# Drive_7seg.net
KiCad netlist of a schematic drawn in EAGLE
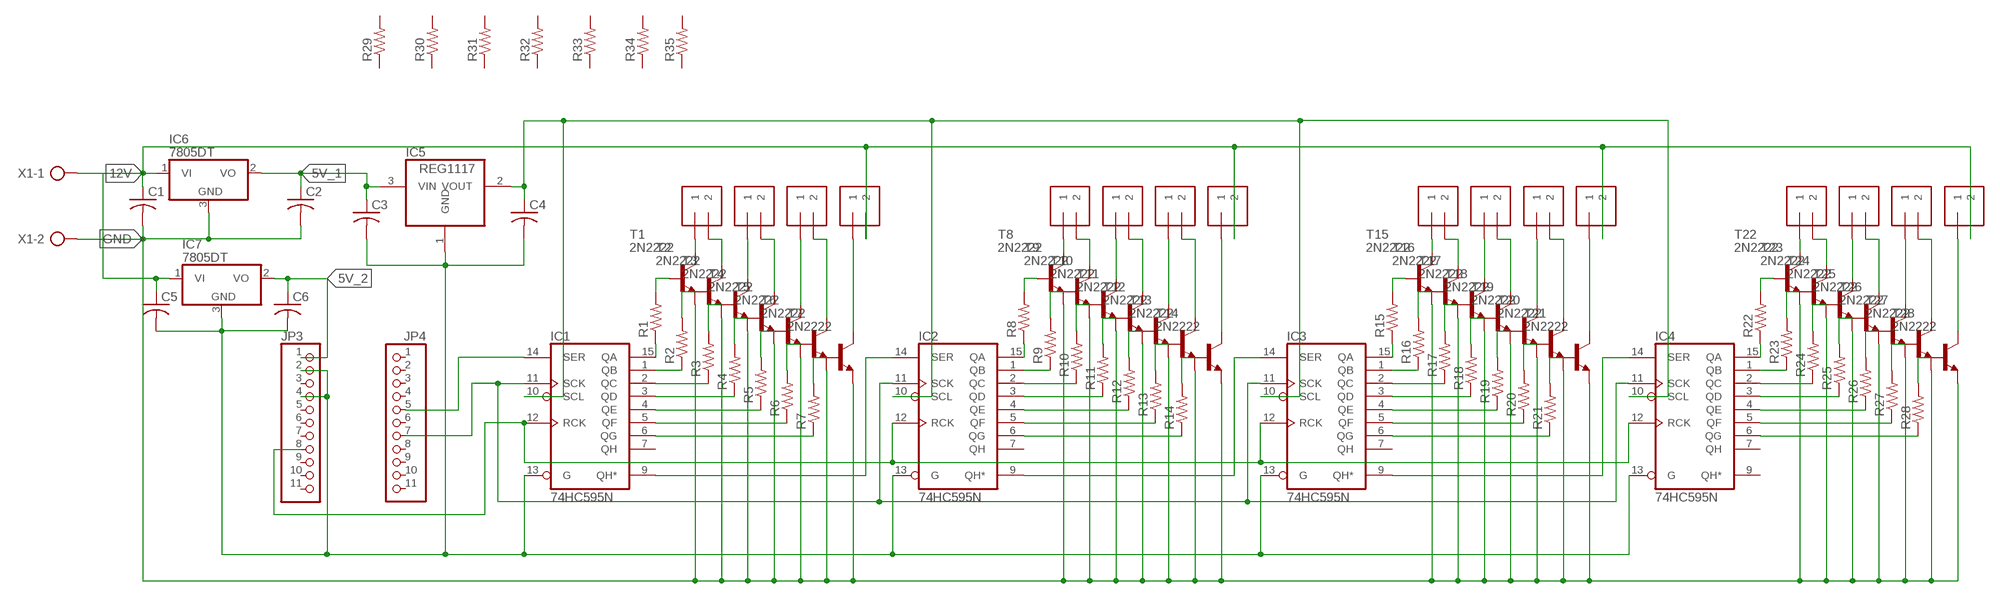
[diagram p0: schematic, sheet 1]

(export (version "E")
  (design (tool "Eeschema 10.0.6"))
  (components
    (comp (ref "C1")
      (value "C-USC0805K")
      (footprint "eagle-import:C0805K")
      (libsource (lib "eagle-import") (part "C-USC0805K"))
    )
    (comp (ref "C2")
      (value "C-USC0805K")
      (footprint "eagle-import:C0805K")
      (libsource (lib "eagle-import") (part "C-USC0805K"))
    )
    (comp (ref "C3")
      (value "C-USC0805K")
      (footprint "eagle-import:C0805K")
      (libsource (lib "eagle-import") (part "C-USC0805K"))
    )
    (comp (ref "C4")
      (value "C-USC0805K")
      (footprint "eagle-import:C0805K")
      (libsource (lib "eagle-import") (part "C-USC0805K"))
    )
    (comp (ref "C5")
      (value "C-USC0805K")
      (footprint "eagle-import:C0805K")
      (libsource (lib "eagle-import") (part "C-USC0805K"))
    )
    (comp (ref "C6")
      (value "C-USC0805K")
      (footprint "eagle-import:C0805K")
      (libsource (lib "eagle-import") (part "C-USC0805K"))
    )
    (comp (ref "IC1")
      (value "74HC595N")
      (footprint "eagle-import:DIL16")
      (libsource (lib "eagle-import") (part "74595NHC"))
    )
    (comp (ref "IC2")
      (value "74HC595N")
      (footprint "eagle-import:DIL16")
      (libsource (lib "eagle-import") (part "74595NHC"))
    )
    (comp (ref "IC3")
      (value "74HC595N")
      (footprint "eagle-import:DIL16")
      (libsource (lib "eagle-import") (part "74595NHC"))
    )
    (comp (ref "IC4")
      (value "74HC595N")
      (footprint "eagle-import:DIL16")
      (libsource (lib "eagle-import") (part "74595NHC"))
    )
    (comp (ref "IC5")
      (value "REG1117")
      (footprint "eagle-import:SOT223")
      (libsource (lib "eagle-import") (part "REG1117"))
    )
    (comp (ref "IC6")
      (value "7805DT")
      (footprint "eagle-import:TO252")
      (libsource (lib "eagle-import") (part "78DT05"))
    )
    (comp (ref "IC7")
      (value "7805DT")
      (footprint "eagle-import:TO252")
      (libsource (lib "eagle-import") (part "78DT05"))
    )
    (comp (ref "J1")
      (value "1X2-3.5MM")
      (footprint "eagle-import:1X2-3.5MM")
      (libsource (lib "eagle-import") (part "1X2-3.5MM"))
    )
    (comp (ref "J2")
      (value "1X2-3.5MM")
      (footprint "eagle-import:1X2-3.5MM")
      (libsource (lib "eagle-import") (part "1X2-3.5MM"))
    )
    (comp (ref "J3")
      (value "1X2-3.5MM")
      (footprint "eagle-import:1X2-3.5MM")
      (libsource (lib "eagle-import") (part "1X2-3.5MM"))
    )
    (comp (ref "J4")
      (value "1X2-3.5MM")
      (footprint "eagle-import:1X2-3.5MM")
      (libsource (lib "eagle-import") (part "1X2-3.5MM"))
    )
    (comp (ref "J5")
      (value "1X2-3.5MM")
      (footprint "eagle-import:1X2-3.5MM")
      (libsource (lib "eagle-import") (part "1X2-3.5MM"))
    )
    (comp (ref "J6")
      (value "1X2-3.5MM")
      (footprint "eagle-import:1X2-3.5MM")
      (libsource (lib "eagle-import") (part "1X2-3.5MM"))
    )
    (comp (ref "J7")
      (value "1X2-3.5MM")
      (footprint "eagle-import:1X2-3.5MM")
      (libsource (lib "eagle-import") (part "1X2-3.5MM"))
    )
    (comp (ref "J8")
      (value "1X2-3.5MM")
      (footprint "eagle-import:1X2-3.5MM")
      (libsource (lib "eagle-import") (part "1X2-3.5MM"))
    )
    (comp (ref "J9")
      (value "1X2-3.5MM")
      (footprint "eagle-import:1X2-3.5MM")
      (libsource (lib "eagle-import") (part "1X2-3.5MM"))
    )
    (comp (ref "J10")
      (value "1X2-3.5MM")
      (footprint "eagle-import:1X2-3.5MM")
      (libsource (lib "eagle-import") (part "1X2-3.5MM"))
    )
    (comp (ref "J11")
      (value "1X2-3.5MM")
      (footprint "eagle-import:1X2-3.5MM")
      (libsource (lib "eagle-import") (part "1X2-3.5MM"))
    )
    (comp (ref "J12")
      (value "1X2-3.5MM")
      (footprint "eagle-import:1X2-3.5MM")
      (libsource (lib "eagle-import") (part "1X2-3.5MM"))
    )
    (comp (ref "J13")
      (value "1X2-3.5MM")
      (footprint "eagle-import:1X2-3.5MM")
      (libsource (lib "eagle-import") (part "1X2-3.5MM"))
    )
    (comp (ref "J14")
      (value "1X2-3.5MM")
      (footprint "eagle-import:1X2-3.5MM")
      (libsource (lib "eagle-import") (part "1X2-3.5MM"))
    )
    (comp (ref "J15")
      (value "1X2-3.5MM")
      (footprint "eagle-import:1X2-3.5MM")
      (libsource (lib "eagle-import") (part "1X2-3.5MM"))
    )
    (comp (ref "J16")
      (value "1X2-3.5MM")
      (footprint "eagle-import:1X2-3.5MM")
      (libsource (lib "eagle-import") (part "1X2-3.5MM"))
    )
    (comp (ref "JP3")
      (value "PINHD-1X11")
      (footprint "eagle-import:1X11")
      (libsource (lib "eagle-import") (part "PINHD-1X11"))
    )
    (comp (ref "JP4")
      (value "PINHD-1X11")
      (footprint "eagle-import:1X11")
      (libsource (lib "eagle-import") (part "PINHD-1X11"))
    )
    (comp (ref "R1")
      (value "R-US_0204/7")
      (footprint "eagle-import:0204_7")
      (libsource (lib "eagle-import") (part "R-US_0204/7"))
    )
    (comp (ref "R2")
      (value "R-US_0204/7")
      (footprint "eagle-import:0204_7")
      (libsource (lib "eagle-import") (part "R-US_0204/7"))
    )
    (comp (ref "R3")
      (value "R-US_0204/7")
      (footprint "eagle-import:0204_7")
      (libsource (lib "eagle-import") (part "R-US_0204/7"))
    )
    (comp (ref "R4")
      (value "R-US_0204/7")
      (footprint "eagle-import:0204_7")
      (libsource (lib "eagle-import") (part "R-US_0204/7"))
    )
    (comp (ref "R5")
      (value "R-US_0204/7")
      (footprint "eagle-import:0204_7")
      (libsource (lib "eagle-import") (part "R-US_0204/7"))
    )
    (comp (ref "R6")
      (value "R-US_0204/7")
      (footprint "eagle-import:0204_7")
      (libsource (lib "eagle-import") (part "R-US_0204/7"))
    )
    (comp (ref "R7")
      (value "R-US_0204/7")
      (footprint "eagle-import:0204_7")
      (libsource (lib "eagle-import") (part "R-US_0204/7"))
    )
    (comp (ref "R8")
      (value "R-US_0204/7")
      (footprint "eagle-import:0204_7")
      (libsource (lib "eagle-import") (part "R-US_0204/7"))
    )
    (comp (ref "R9")
      (value "R-US_0204/7")
      (footprint "eagle-import:0204_7")
      (libsource (lib "eagle-import") (part "R-US_0204/7"))
    )
    (comp (ref "R10")
      (value "R-US_0204/7")
      (footprint "eagle-import:0204_7")
      (libsource (lib "eagle-import") (part "R-US_0204/7"))
    )
    (comp (ref "R11")
      (value "R-US_0204/7")
      (footprint "eagle-import:0204_7")
      (libsource (lib "eagle-import") (part "R-US_0204/7"))
    )
    (comp (ref "R12")
      (value "R-US_0204/7")
      (footprint "eagle-import:0204_7")
      (libsource (lib "eagle-import") (part "R-US_0204/7"))
    )
    (comp (ref "R13")
      (value "R-US_0204/7")
      (footprint "eagle-import:0204_7")
      (libsource (lib "eagle-import") (part "R-US_0204/7"))
    )
    (comp (ref "R14")
      (value "R-US_0204/7")
      (footprint "eagle-import:0204_7")
      (libsource (lib "eagle-import") (part "R-US_0204/7"))
    )
    (comp (ref "R15")
      (value "R-US_0204/7")
      (footprint "eagle-import:0204_7")
      (libsource (lib "eagle-import") (part "R-US_0204/7"))
    )
    (comp (ref "R16")
      (value "R-US_0204/7")
      (footprint "eagle-import:0204_7")
      (libsource (lib "eagle-import") (part "R-US_0204/7"))
    )
    (comp (ref "R17")
      (value "R-US_0204/7")
      (footprint "eagle-import:0204_7")
      (libsource (lib "eagle-import") (part "R-US_0204/7"))
    )
    (comp (ref "R18")
      (value "R-US_0204/7")
      (footprint "eagle-import:0204_7")
      (libsource (lib "eagle-import") (part "R-US_0204/7"))
    )
    (comp (ref "R19")
      (value "R-US_0204/7")
      (footprint "eagle-import:0204_7")
      (libsource (lib "eagle-import") (part "R-US_0204/7"))
    )
    (comp (ref "R20")
      (value "R-US_0204/7")
      (footprint "eagle-import:0204_7")
      (libsource (lib "eagle-import") (part "R-US_0204/7"))
    )
    (comp (ref "R21")
      (value "R-US_0204/7")
      (footprint "eagle-import:0204_7")
      (libsource (lib "eagle-import") (part "R-US_0204/7"))
    )
    (comp (ref "R22")
      (value "R-US_0204/7")
      (footprint "eagle-import:0204_7")
      (libsource (lib "eagle-import") (part "R-US_0204/7"))
    )
    (comp (ref "R23")
      (value "R-US_0204/7")
      (footprint "eagle-import:0204_7")
      (libsource (lib "eagle-import") (part "R-US_0204/7"))
    )
    (comp (ref "R24")
      (value "R-US_0204/7")
      (footprint "eagle-import:0204_7")
      (libsource (lib "eagle-import") (part "R-US_0204/7"))
    )
    (comp (ref "R25")
      (value "R-US_0204/7")
      (footprint "eagle-import:0204_7")
      (libsource (lib "eagle-import") (part "R-US_0204/7"))
    )
    (comp (ref "R26")
      (value "R-US_0204/7")
      (footprint "eagle-import:0204_7")
      (libsource (lib "eagle-import") (part "R-US_0204/7"))
    )
    (comp (ref "R27")
      (value "R-US_0204/7")
      (footprint "eagle-import:0204_7")
      (libsource (lib "eagle-import") (part "R-US_0204/7"))
    )
    (comp (ref "R28")
      (value "R-US_0204/7")
      (footprint "eagle-import:0204_7")
      (libsource (lib "eagle-import") (part "R-US_0204/7"))
    )
    (comp (ref "R29")
      (value "R-US_0204/7")
      (footprint "eagle-import:0204_7")
      (libsource (lib "eagle-import") (part "R-US_0204/7"))
    )
    (comp (ref "R30")
      (value "R-US_0204/7")
      (footprint "eagle-import:0204_7")
      (libsource (lib "eagle-import") (part "R-US_0204/7"))
    )
    (comp (ref "R31")
      (value "R-US_0204/7")
      (footprint "eagle-import:0204_7")
      (libsource (lib "eagle-import") (part "R-US_0204/7"))
    )
    (comp (ref "R32")
      (value "R-US_0204/7")
      (footprint "eagle-import:0204_7")
      (libsource (lib "eagle-import") (part "R-US_0204/7"))
    )
    (comp (ref "R33")
      (value "R-US_0204/7")
      (footprint "eagle-import:0204_7")
      (libsource (lib "eagle-import") (part "R-US_0204/7"))
    )
    (comp (ref "R34")
      (value "R-US_0204/7")
      (footprint "eagle-import:0204_7")
      (libsource (lib "eagle-import") (part "R-US_0204/7"))
    )
    (comp (ref "R35")
      (value "R-US_0204/7")
      (footprint "eagle-import:0204_7")
      (libsource (lib "eagle-import") (part "R-US_0204/7"))
    )
    (comp (ref "T1")
      (value "2N2222")
      (footprint "eagle-import:TO92-EBC-OVAL")
      (libsource (lib "eagle-import") (part "2N2222"))
    )
    (comp (ref "T2")
      (value "2N2222")
      (footprint "eagle-import:TO92-EBC-OVAL")
      (libsource (lib "eagle-import") (part "2N2222"))
    )
    (comp (ref "T3")
      (value "2N2222")
      (footprint "eagle-import:TO92-EBC-OVAL")
      (libsource (lib "eagle-import") (part "2N2222"))
    )
    (comp (ref "T4")
      (value "2N2222")
      (footprint "eagle-import:TO92-EBC-OVAL")
      (libsource (lib "eagle-import") (part "2N2222"))
    )
    (comp (ref "T5")
      (value "2N2222")
      (footprint "eagle-import:TO92-EBC-OVAL")
      (libsource (lib "eagle-import") (part "2N2222"))
    )
    (comp (ref "T6")
      (value "2N2222")
      (footprint "eagle-import:TO92-EBC-OVAL")
      (libsource (lib "eagle-import") (part "2N2222"))
    )
    (comp (ref "T7")
      (value "2N2222")
      (footprint "eagle-import:TO92-EBC-OVAL")
      (libsource (lib "eagle-import") (part "2N2222"))
    )
    (comp (ref "T8")
      (value "2N2222")
      (footprint "eagle-import:TO92-EBC-OVAL")
      (libsource (lib "eagle-import") (part "2N2222"))
    )
    (comp (ref "T9")
      (value "2N2222")
      (footprint "eagle-import:TO92-EBC-OVAL")
      (libsource (lib "eagle-import") (part "2N2222"))
    )
    (comp (ref "T10")
      (value "2N2222")
      (footprint "eagle-import:TO92-EBC-OVAL")
      (libsource (lib "eagle-import") (part "2N2222"))
    )
    (comp (ref "T11")
      (value "2N2222")
      (footprint "eagle-import:TO92-EBC-OVAL")
      (libsource (lib "eagle-import") (part "2N2222"))
    )
    (comp (ref "T12")
      (value "2N2222")
      (footprint "eagle-import:TO92-EBC-OVAL")
      (libsource (lib "eagle-import") (part "2N2222"))
    )
    (comp (ref "T13")
      (value "2N2222")
      (footprint "eagle-import:TO92-EBC-OVAL")
      (libsource (lib "eagle-import") (part "2N2222"))
    )
    (comp (ref "T14")
      (value "2N2222")
      (footprint "eagle-import:TO92-EBC-OVAL")
      (libsource (lib "eagle-import") (part "2N2222"))
    )
    (comp (ref "T15")
      (value "2N2222")
      (footprint "eagle-import:TO92-EBC-OVAL")
      (libsource (lib "eagle-import") (part "2N2222"))
    )
    (comp (ref "T16")
      (value "2N2222")
      (footprint "eagle-import:TO92-EBC-OVAL")
      (libsource (lib "eagle-import") (part "2N2222"))
    )
    (comp (ref "T17")
      (value "2N2222")
      (footprint "eagle-import:TO92-EBC-OVAL")
      (libsource (lib "eagle-import") (part "2N2222"))
    )
    (comp (ref "T18")
      (value "2N2222")
      (footprint "eagle-import:TO92-EBC-OVAL")
      (libsource (lib "eagle-import") (part "2N2222"))
    )
    (comp (ref "T19")
      (value "2N2222")
      (footprint "eagle-import:TO92-EBC-OVAL")
      (libsource (lib "eagle-import") (part "2N2222"))
    )
    (comp (ref "T20")
      (value "2N2222")
      (footprint "eagle-import:TO92-EBC-OVAL")
      (libsource (lib "eagle-import") (part "2N2222"))
    )
    (comp (ref "T21")
      (value "2N2222")
      (footprint "eagle-import:TO92-EBC-OVAL")
      (libsource (lib "eagle-import") (part "2N2222"))
    )
    (comp (ref "T22")
      (value "2N2222")
      (footprint "eagle-import:TO92-EBC-OVAL")
      (libsource (lib "eagle-import") (part "2N2222"))
    )
    (comp (ref "T23")
      (value "2N2222")
      (footprint "eagle-import:TO92-EBC-OVAL")
      (libsource (lib "eagle-import") (part "2N2222"))
    )
    (comp (ref "T24")
      (value "2N2222")
      (footprint "eagle-import:TO92-EBC-OVAL")
      (libsource (lib "eagle-import") (part "2N2222"))
    )
    (comp (ref "T25")
      (value "2N2222")
      (footprint "eagle-import:TO92-EBC-OVAL")
      (libsource (lib "eagle-import") (part "2N2222"))
    )
    (comp (ref "T26")
      (value "2N2222")
      (footprint "eagle-import:TO92-EBC-OVAL")
      (libsource (lib "eagle-import") (part "2N2222"))
    )
    (comp (ref "T27")
      (value "2N2222")
      (footprint "eagle-import:TO92-EBC-OVAL")
      (libsource (lib "eagle-import") (part "2N2222"))
    )
    (comp (ref "T28")
      (value "2N2222")
      (footprint "eagle-import:TO92-EBC-OVAL")
      (libsource (lib "eagle-import") (part "2N2222"))
    )
    (comp (ref "X1")
      (value "AK300/2")
      (footprint "eagle-import:AK300_2")
      (libsource (lib "eagle-import") (part "AK300/2"))
    )
  )
  (nets
    (net (code "1") (name "5V_1") (class "Default")
      (node (ref "C2") (pin "1") (pinfunction "1_1") (pintype "passive"))
      (node (ref "C3") (pin "1") (pinfunction "1_1") (pintype "passive"))
      (node (ref "IC5") (pin "3") (pinfunction "VIN_3") (pintype "input"))
      (node (ref "IC6") (pin "2") (pinfunction "VO_2") (pintype "passive"))
    )
    (net (code "2") (name "5V_2") (class "Default")
      (node (ref "C6") (pin "1") (pinfunction "1_1") (pintype "passive"))
      (node (ref "IC7") (pin "2") (pinfunction "VO_2") (pintype "passive"))
      (node (ref "JP3") (pin "1") (pinfunction "1_1") (pintype "passive"))
    )
    (net (code "3") (name "12V") (class "Default")
      (node (ref "C1") (pin "1") (pinfunction "1_1") (pintype "passive"))
      (node (ref "C5") (pin "1") (pinfunction "1_1") (pintype "passive"))
      (node (ref "IC6") (pin "1") (pinfunction "VI_1") (pintype "input"))
      (node (ref "IC7") (pin "1") (pinfunction "VI_1") (pintype "input"))
      (node (ref "J12") (pin "2") (pinfunction "2_2") (pintype "passive"))
      (node (ref "J16") (pin "2") (pinfunction "2_2") (pintype "passive"))
      (node (ref "J4") (pin "2") (pinfunction "2_2") (pintype "passive"))
      (node (ref "J8") (pin "2") (pinfunction "2_2") (pintype "passive"))
      (node (ref "X1") (pin "1") (pinfunction "KL_1") (pintype "passive"))
    )
    (net (code "4") (name "GND") (class "Default")
      (node (ref "C1") (pin "2") (pinfunction "2_2") (pintype "passive"))
      (node (ref "C2") (pin "2") (pinfunction "2_2") (pintype "passive"))
      (node (ref "C3") (pin "2") (pinfunction "2_2") (pintype "passive"))
      (node (ref "C4") (pin "2") (pinfunction "2_2") (pintype "passive"))
      (node (ref "C5") (pin "2") (pinfunction "2_2") (pintype "passive"))
      (node (ref "C6") (pin "2") (pinfunction "2_2") (pintype "passive"))
      (node (ref "IC1") (pin "13") (pinfunction "G_13") (pintype "input"))
      (node (ref "IC2") (pin "13") (pinfunction "G_13") (pintype "input"))
      (node (ref "IC3") (pin "13") (pinfunction "G_13") (pintype "input"))
      (node (ref "IC4") (pin "13") (pinfunction "G_13") (pintype "input"))
      (node (ref "IC5") (pin "1") (pinfunction "GND_1") (pintype "power_in"))
      (node (ref "IC6") (pin "3") (pinfunction "GND_3") (pintype "passive"))
      (node (ref "IC7") (pin "3") (pinfunction "GND_3") (pintype "passive"))
      (node (ref "JP3") (pin "2") (pinfunction "2_2") (pintype "passive"))
      (node (ref "JP3") (pin "4") (pinfunction "4_4") (pintype "passive"))
      (node (ref "T1") (pin "E") (pinfunction "E_E") (pintype "passive"))
      (node (ref "T10") (pin "E") (pinfunction "E_E") (pintype "passive"))
      (node (ref "T11") (pin "E") (pinfunction "E_E") (pintype "passive"))
      (node (ref "T12") (pin "E") (pinfunction "E_E") (pintype "passive"))
      (node (ref "T13") (pin "E") (pinfunction "E_E") (pintype "passive"))
      (node (ref "T14") (pin "E") (pinfunction "E_E") (pintype "passive"))
      (node (ref "T15") (pin "E") (pinfunction "E_E") (pintype "passive"))
      (node (ref "T16") (pin "E") (pinfunction "E_E") (pintype "passive"))
      (node (ref "T17") (pin "E") (pinfunction "E_E") (pintype "passive"))
      (node (ref "T18") (pin "E") (pinfunction "E_E") (pintype "passive"))
      (node (ref "T19") (pin "E") (pinfunction "E_E") (pintype "passive"))
      (node (ref "T2") (pin "E") (pinfunction "E_E") (pintype "passive"))
      (node (ref "T20") (pin "E") (pinfunction "E_E") (pintype "passive"))
      (node (ref "T21") (pin "E") (pinfunction "E_E") (pintype "passive"))
      (node (ref "T22") (pin "E") (pinfunction "E_E") (pintype "passive"))
      (node (ref "T23") (pin "E") (pinfunction "E_E") (pintype "passive"))
      (node (ref "T24") (pin "E") (pinfunction "E_E") (pintype "passive"))
      (node (ref "T25") (pin "E") (pinfunction "E_E") (pintype "passive"))
      (node (ref "T26") (pin "E") (pinfunction "E_E") (pintype "passive"))
      (node (ref "T27") (pin "E") (pinfunction "E_E") (pintype "passive"))
      (node (ref "T28") (pin "E") (pinfunction "E_E") (pintype "passive"))
      (node (ref "T3") (pin "E") (pinfunction "E_E") (pintype "passive"))
      (node (ref "T4") (pin "E") (pinfunction "E_E") (pintype "passive"))
      (node (ref "T5") (pin "E") (pinfunction "E_E") (pintype "passive"))
      (node (ref "T6") (pin "E") (pinfunction "E_E") (pintype "passive"))
      (node (ref "T7") (pin "E") (pinfunction "E_E") (pintype "passive"))
      (node (ref "T8") (pin "E") (pinfunction "E_E") (pintype "passive"))
      (node (ref "T9") (pin "E") (pinfunction "E_E") (pintype "passive"))
      (node (ref "X1") (pin "2") (pinfunction "KL_2") (pintype "passive"))
    )
    (net (code "5") (name "Net-(IC1A-QA)") (class "Default")
      (node (ref "IC1") (pin "15") (pinfunction "QA_15") (pintype "tri_state"))
      (node (ref "R1") (pin "1") (pinfunction "1_1") (pintype "passive"))
    )
    (net (code "6") (name "Net-(IC1A-QB)") (class "Default")
      (node (ref "IC1") (pin "1") (pinfunction "QB_1") (pintype "tri_state"))
      (node (ref "R2") (pin "1") (pinfunction "1_1") (pintype "passive"))
    )
    (net (code "7") (name "Net-(IC1A-QC)") (class "Default")
      (node (ref "IC1") (pin "2") (pinfunction "QC_2") (pintype "tri_state"))
      (node (ref "R3") (pin "1") (pinfunction "1_1") (pintype "passive"))
    )
    (net (code "8") (name "Net-(IC1A-QD)") (class "Default")
      (node (ref "IC1") (pin "3") (pinfunction "QD_3") (pintype "tri_state"))
      (node (ref "R4") (pin "1") (pinfunction "1_1") (pintype "passive"))
    )
    (net (code "9") (name "Net-(IC1A-QE)") (class "Default")
      (node (ref "IC1") (pin "4") (pinfunction "QE_4") (pintype "tri_state"))
      (node (ref "R5") (pin "1") (pinfunction "1_1") (pintype "passive"))
    )
    (net (code "10") (name "Net-(IC1A-QF)") (class "Default")
      (node (ref "IC1") (pin "5") (pinfunction "QF_5") (pintype "tri_state"))
      (node (ref "R6") (pin "1") (pinfunction "1_1") (pintype "passive"))
    )
    (net (code "11") (name "Net-(IC1A-QG)") (class "Default")
      (node (ref "IC1") (pin "6") (pinfunction "QG_6") (pintype "tri_state"))
      (node (ref "R7") (pin "1") (pinfunction "1_1") (pintype "passive"))
    )
    (net (code "12") (name "Net-(IC1A-QH*)") (class "Default")
      (node (ref "IC1") (pin "9") (pinfunction "QH*_9") (pintype "tri_state"))
      (node (ref "IC2") (pin "14") (pinfunction "SER_14") (pintype "input"))
    )
    (net (code "13") (name "Net-(IC1A-RCK)") (class "Default")
      (node (ref "IC1") (pin "12") (pinfunction "RCK_12") (pintype "input"))
      (node (ref "IC2") (pin "12") (pinfunction "RCK_12") (pintype "input"))
      (node (ref "IC3") (pin "12") (pinfunction "RCK_12") (pintype "input"))
      (node (ref "IC4") (pin "12") (pinfunction "RCK_12") (pintype "input"))
      (node (ref "JP3") (pin "8") (pinfunction "8_8") (pintype "passive"))
    )
    (net (code "14") (name "Net-(IC1A-SCK)") (class "Default")
      (node (ref "IC1") (pin "11") (pinfunction "SCK_11") (pintype "input"))
      (node (ref "IC2") (pin "11") (pinfunction "SCK_11") (pintype "input"))
      (node (ref "IC3") (pin "11") (pinfunction "SCK_11") (pintype "input"))
      (node (ref "IC4") (pin "11") (pinfunction "SCK_11") (pintype "input"))
      (node (ref "JP4") (pin "7") (pinfunction "7_7") (pintype "passive"))
    )
    (net (code "15") (name "Net-(IC1A-SCL)") (class "Default")
      (node (ref "C4") (pin "1") (pinfunction "1_1") (pintype "passive"))
      (node (ref "IC1") (pin "10") (pinfunction "SCL_10") (pintype "input"))
      (node (ref "IC2") (pin "10") (pinfunction "SCL_10") (pintype "input"))
      (node (ref "IC3") (pin "10") (pinfunction "SCL_10") (pintype "input"))
      (node (ref "IC4") (pin "10") (pinfunction "SCL_10") (pintype "input"))
      (node (ref "IC5") (pin "2") (pinfunction "VOUT_2") (pintype "output"))
    )
    (net (code "16") (name "Net-(IC1A-SER)") (class "Default")
      (node (ref "IC1") (pin "14") (pinfunction "SER_14") (pintype "input"))
      (node (ref "JP4") (pin "5") (pinfunction "5_5") (pintype "passive"))
    )
    (net (code "17") (name "Net-(IC2A-QA)") (class "Default")
      (node (ref "IC2") (pin "15") (pinfunction "QA_15") (pintype "tri_state"))
      (node (ref "R8") (pin "1") (pinfunction "1_1") (pintype "passive"))
    )
    (net (code "18") (name "Net-(IC2A-QB)") (class "Default")
      (node (ref "IC2") (pin "1") (pinfunction "QB_1") (pintype "tri_state"))
      (node (ref "R9") (pin "1") (pinfunction "1_1") (pintype "passive"))
    )
    (net (code "19") (name "Net-(IC2A-QC)") (class "Default")
      (node (ref "IC2") (pin "2") (pinfunction "QC_2") (pintype "tri_state"))
      (node (ref "R10") (pin "1") (pinfunction "1_1") (pintype "passive"))
    )
    (net (code "20") (name "Net-(IC2A-QD)") (class "Default")
      (node (ref "IC2") (pin "3") (pinfunction "QD_3") (pintype "tri_state"))
      (node (ref "R11") (pin "1") (pinfunction "1_1") (pintype "passive"))
    )
    (net (code "21") (name "Net-(IC2A-QE)") (class "Default")
      (node (ref "IC2") (pin "4") (pinfunction "QE_4") (pintype "tri_state"))
      (node (ref "R12") (pin "1") (pinfunction "1_1") (pintype "passive"))
    )
    (net (code "22") (name "Net-(IC2A-QF)") (class "Default")
      (node (ref "IC2") (pin "5") (pinfunction "QF_5") (pintype "tri_state"))
      (node (ref "R13") (pin "1") (pinfunction "1_1") (pintype "passive"))
    )
    (net (code "23") (name "Net-(IC2A-QG)") (class "Default")
      (node (ref "IC2") (pin "6") (pinfunction "QG_6") (pintype "tri_state"))
      (node (ref "R14") (pin "1") (pinfunction "1_1") (pintype "passive"))
    )
    (net (code "24") (name "Net-(IC2A-QH*)") (class "Default")
      (node (ref "IC2") (pin "9") (pinfunction "QH*_9") (pintype "tri_state"))
      (node (ref "IC3") (pin "14") (pinfunction "SER_14") (pintype "input"))
    )
    (net (code "25") (name "Net-(IC3A-QA)") (class "Default")
      (node (ref "IC3") (pin "15") (pinfunction "QA_15") (pintype "tri_state"))
      (node (ref "R15") (pin "1") (pinfunction "1_1") (pintype "passive"))
    )
    (net (code "26") (name "Net-(IC3A-QB)") (class "Default")
      (node (ref "IC3") (pin "1") (pinfunction "QB_1") (pintype "tri_state"))
      (node (ref "R16") (pin "1") (pinfunction "1_1") (pintype "passive"))
    )
    (net (code "27") (name "Net-(IC3A-QC)") (class "Default")
      (node (ref "IC3") (pin "2") (pinfunction "QC_2") (pintype "tri_state"))
      (node (ref "R17") (pin "1") (pinfunction "1_1") (pintype "passive"))
    )
    (net (code "28") (name "Net-(IC3A-QD)") (class "Default")
      (node (ref "IC3") (pin "3") (pinfunction "QD_3") (pintype "tri_state"))
      (node (ref "R18") (pin "1") (pinfunction "1_1") (pintype "passive"))
    )
    (net (code "29") (name "Net-(IC3A-QE)") (class "Default")
      (node (ref "IC3") (pin "4") (pinfunction "QE_4") (pintype "tri_state"))
      (node (ref "R19") (pin "1") (pinfunction "1_1") (pintype "passive"))
    )
    (net (code "30") (name "Net-(IC3A-QF)") (class "Default")
      (node (ref "IC3") (pin "5") (pinfunction "QF_5") (pintype "tri_state"))
      (node (ref "R20") (pin "1") (pinfunction "1_1") (pintype "passive"))
    )
    (net (code "31") (name "Net-(IC3A-QG)") (class "Default")
      (node (ref "IC3") (pin "6") (pinfunction "QG_6") (pintype "tri_state"))
      (node (ref "R21") (pin "1") (pinfunction "1_1") (pintype "passive"))
    )
    (net (code "32") (name "Net-(IC3A-QH*)") (class "Default")
      (node (ref "IC3") (pin "9") (pinfunction "QH*_9") (pintype "tri_state"))
      (node (ref "IC4") (pin "14") (pinfunction "SER_14") (pintype "input"))
    )
    (net (code "33") (name "Net-(IC4A-QA)") (class "Default")
      (node (ref "IC4") (pin "15") (pinfunction "QA_15") (pintype "tri_state"))
      (node (ref "R22") (pin "1") (pinfunction "1_1") (pintype "passive"))
    )
    (net (code "34") (name "Net-(IC4A-QB)") (class "Default")
      (node (ref "IC4") (pin "1") (pinfunction "QB_1") (pintype "tri_state"))
      (node (ref "R23") (pin "1") (pinfunction "1_1") (pintype "passive"))
    )
    (net (code "35") (name "Net-(IC4A-QC)") (class "Default")
      (node (ref "IC4") (pin "2") (pinfunction "QC_2") (pintype "tri_state"))
      (node (ref "R24") (pin "1") (pinfunction "1_1") (pintype "passive"))
    )
    (net (code "36") (name "Net-(IC4A-QD)") (class "Default")
      (node (ref "IC4") (pin "3") (pinfunction "QD_3") (pintype "tri_state"))
      (node (ref "R25") (pin "1") (pinfunction "1_1") (pintype "passive"))
    )
    (net (code "37") (name "Net-(IC4A-QE)") (class "Default")
      (node (ref "IC4") (pin "4") (pinfunction "QE_4") (pintype "tri_state"))
      (node (ref "R26") (pin "1") (pinfunction "1_1") (pintype "passive"))
    )
    (net (code "38") (name "Net-(IC4A-QF)") (class "Default")
      (node (ref "IC4") (pin "5") (pinfunction "QF_5") (pintype "tri_state"))
      (node (ref "R27") (pin "1") (pinfunction "1_1") (pintype "passive"))
    )
    (net (code "39") (name "Net-(IC4A-QG)") (class "Default")
      (node (ref "IC4") (pin "6") (pinfunction "QG_6") (pintype "tri_state"))
      (node (ref "R28") (pin "1") (pinfunction "1_1") (pintype "passive"))
    )
    (net (code "40") (name "Net-(J1-Pad1)") (class "Default")
      (node (ref "J1") (pin "1") (pinfunction "1_1") (pintype "passive"))
      (node (ref "T1") (pin "C") (pinfunction "C_C") (pintype "passive"))
    )
    (net (code "41") (name "Net-(J1-Pad2)") (class "Default")
      (node (ref "J1") (pin "2") (pinfunction "2_2") (pintype "passive"))
      (node (ref "T2") (pin "C") (pinfunction "C_C") (pintype "passive"))
    )
    (net (code "42") (name "Net-(J2-Pad1)") (class "Default")
      (node (ref "J2") (pin "1") (pinfunction "1_1") (pintype "passive"))
      (node (ref "T3") (pin "C") (pinfunction "C_C") (pintype "passive"))
    )
    (net (code "43") (name "Net-(J2-Pad2)") (class "Default")
      (node (ref "J2") (pin "2") (pinfunction "2_2") (pintype "passive"))
      (node (ref "T4") (pin "C") (pinfunction "C_C") (pintype "passive"))
    )
    (net (code "44") (name "Net-(J3-Pad1)") (class "Default")
      (node (ref "J3") (pin "1") (pinfunction "1_1") (pintype "passive"))
      (node (ref "T5") (pin "C") (pinfunction "C_C") (pintype "passive"))
    )
    (net (code "45") (name "Net-(J3-Pad2)") (class "Default")
      (node (ref "J3") (pin "2") (pinfunction "2_2") (pintype "passive"))
      (node (ref "T6") (pin "C") (pinfunction "C_C") (pintype "passive"))
    )
    (net (code "46") (name "Net-(J4-Pad1)") (class "Default")
      (node (ref "J4") (pin "1") (pinfunction "1_1") (pintype "passive"))
      (node (ref "T7") (pin "C") (pinfunction "C_C") (pintype "passive"))
    )
    (net (code "47") (name "Net-(J5-Pad1)") (class "Default")
      (node (ref "J5") (pin "1") (pinfunction "1_1") (pintype "passive"))
      (node (ref "T8") (pin "C") (pinfunction "C_C") (pintype "passive"))
    )
    (net (code "48") (name "Net-(J5-Pad2)") (class "Default")
      (node (ref "J5") (pin "2") (pinfunction "2_2") (pintype "passive"))
      (node (ref "T9") (pin "C") (pinfunction "C_C") (pintype "passive"))
    )
    (net (code "49") (name "Net-(J6-Pad1)") (class "Default")
      (node (ref "J6") (pin "1") (pinfunction "1_1") (pintype "passive"))
      (node (ref "T10") (pin "C") (pinfunction "C_C") (pintype "passive"))
    )
    (net (code "50") (name "Net-(J6-Pad2)") (class "Default")
      (node (ref "J6") (pin "2") (pinfunction "2_2") (pintype "passive"))
      (node (ref "T11") (pin "C") (pinfunction "C_C") (pintype "passive"))
    )
    (net (code "51") (name "Net-(J7-Pad1)") (class "Default")
      (node (ref "J7") (pin "1") (pinfunction "1_1") (pintype "passive"))
      (node (ref "T12") (pin "C") (pinfunction "C_C") (pintype "passive"))
    )
    (net (code "52") (name "Net-(J7-Pad2)") (class "Default")
      (node (ref "J7") (pin "2") (pinfunction "2_2") (pintype "passive"))
      (node (ref "T13") (pin "C") (pinfunction "C_C") (pintype "passive"))
    )
    (net (code "53") (name "Net-(J8-Pad1)") (class "Default")
      (node (ref "J8") (pin "1") (pinfunction "1_1") (pintype "passive"))
      (node (ref "T14") (pin "C") (pinfunction "C_C") (pintype "passive"))
    )
    (net (code "54") (name "Net-(J9-Pad1)") (class "Default")
      (node (ref "J9") (pin "1") (pinfunction "1_1") (pintype "passive"))
      (node (ref "T15") (pin "C") (pinfunction "C_C") (pintype "passive"))
    )
    (net (code "55") (name "Net-(J9-Pad2)") (class "Default")
      (node (ref "J9") (pin "2") (pinfunction "2_2") (pintype "passive"))
      (node (ref "T16") (pin "C") (pinfunction "C_C") (pintype "passive"))
    )
    (net (code "56") (name "Net-(J10-Pad1)") (class "Default")
      (node (ref "J10") (pin "1") (pinfunction "1_1") (pintype "passive"))
      (node (ref "T17") (pin "C") (pinfunction "C_C") (pintype "passive"))
    )
    (net (code "57") (name "Net-(J10-Pad2)") (class "Default")
      (node (ref "J10") (pin "2") (pinfunction "2_2") (pintype "passive"))
      (node (ref "T18") (pin "C") (pinfunction "C_C") (pintype "passive"))
    )
    (net (code "58") (name "Net-(J11-Pad1)") (class "Default")
      (node (ref "J11") (pin "1") (pinfunction "1_1") (pintype "passive"))
      (node (ref "T19") (pin "C") (pinfunction "C_C") (pintype "passive"))
    )
    (net (code "59") (name "Net-(J11-Pad2)") (class "Default")
      (node (ref "J11") (pin "2") (pinfunction "2_2") (pintype "passive"))
      (node (ref "T20") (pin "C") (pinfunction "C_C") (pintype "passive"))
    )
    (net (code "60") (name "Net-(J12-Pad1)") (class "Default")
      (node (ref "J12") (pin "1") (pinfunction "1_1") (pintype "passive"))
      (node (ref "T21") (pin "C") (pinfunction "C_C") (pintype "passive"))
    )
    (net (code "61") (name "Net-(J13-Pad1)") (class "Default")
      (node (ref "J13") (pin "1") (pinfunction "1_1") (pintype "passive"))
      (node (ref "T22") (pin "C") (pinfunction "C_C") (pintype "passive"))
    )
    (net (code "62") (name "Net-(J13-Pad2)") (class "Default")
      (node (ref "J13") (pin "2") (pinfunction "2_2") (pintype "passive"))
      (node (ref "T23") (pin "C") (pinfunction "C_C") (pintype "passive"))
    )
    (net (code "63") (name "Net-(J14-Pad1)") (class "Default")
      (node (ref "J14") (pin "1") (pinfunction "1_1") (pintype "passive"))
      (node (ref "T24") (pin "C") (pinfunction "C_C") (pintype "passive"))
    )
    (net (code "64") (name "Net-(J14-Pad2)") (class "Default")
      (node (ref "J14") (pin "2") (pinfunction "2_2") (pintype "passive"))
      (node (ref "T25") (pin "C") (pinfunction "C_C") (pintype "passive"))
    )
    (net (code "65") (name "Net-(J15-Pad1)") (class "Default")
      (node (ref "J15") (pin "1") (pinfunction "1_1") (pintype "passive"))
      (node (ref "T26") (pin "C") (pinfunction "C_C") (pintype "passive"))
    )
    (net (code "66") (name "Net-(J15-Pad2)") (class "Default")
      (node (ref "J15") (pin "2") (pinfunction "2_2") (pintype "passive"))
      (node (ref "T27") (pin "C") (pinfunction "C_C") (pintype "passive"))
    )
    (net (code "67") (name "Net-(J16-Pad1)") (class "Default")
      (node (ref "J16") (pin "1") (pinfunction "1_1") (pintype "passive"))
      (node (ref "T28") (pin "C") (pinfunction "C_C") (pintype "passive"))
    )
    (net (code "68") (name "Net-(R1-Pad2)") (class "Default")
      (node (ref "R1") (pin "2") (pinfunction "2_2") (pintype "passive"))
      (node (ref "T1") (pin "B") (pinfunction "B_B") (pintype "passive"))
    )
    (net (code "69") (name "Net-(R2-Pad2)") (class "Default")
      (node (ref "R2") (pin "2") (pinfunction "2_2") (pintype "passive"))
      (node (ref "T2") (pin "B") (pinfunction "B_B") (pintype "passive"))
    )
    (net (code "70") (name "Net-(R3-Pad2)") (class "Default")
      (node (ref "R3") (pin "2") (pinfunction "2_2") (pintype "passive"))
      (node (ref "T3") (pin "B") (pinfunction "B_B") (pintype "passive"))
    )
    (net (code "71") (name "Net-(R4-Pad2)") (class "Default")
      (node (ref "R4") (pin "2") (pinfunction "2_2") (pintype "passive"))
      (node (ref "T4") (pin "B") (pinfunction "B_B") (pintype "passive"))
    )
    (net (code "72") (name "Net-(R5-Pad2)") (class "Default")
      (node (ref "R5") (pin "2") (pinfunction "2_2") (pintype "passive"))
      (node (ref "T5") (pin "B") (pinfunction "B_B") (pintype "passive"))
    )
    (net (code "73") (name "Net-(R6-Pad2)") (class "Default")
      (node (ref "R6") (pin "2") (pinfunction "2_2") (pintype "passive"))
      (node (ref "T6") (pin "B") (pinfunction "B_B") (pintype "passive"))
    )
    (net (code "74") (name "Net-(R7-Pad2)") (class "Default")
      (node (ref "R7") (pin "2") (pinfunction "2_2") (pintype "passive"))
      (node (ref "T7") (pin "B") (pinfunction "B_B") (pintype "passive"))
    )
    (net (code "75") (name "Net-(R8-Pad2)") (class "Default")
      (node (ref "R8") (pin "2") (pinfunction "2_2") (pintype "passive"))
      (node (ref "T8") (pin "B") (pinfunction "B_B") (pintype "passive"))
    )
    (net (code "76") (name "Net-(R9-Pad2)") (class "Default")
      (node (ref "R9") (pin "2") (pinfunction "2_2") (pintype "passive"))
      (node (ref "T9") (pin "B") (pinfunction "B_B") (pintype "passive"))
    )
    (net (code "77") (name "Net-(R10-Pad2)") (class "Default")
      (node (ref "R10") (pin "2") (pinfunction "2_2") (pintype "passive"))
      (node (ref "T10") (pin "B") (pinfunction "B_B") (pintype "passive"))
    )
    (net (code "78") (name "Net-(R11-Pad2)") (class "Default")
      (node (ref "R11") (pin "2") (pinfunction "2_2") (pintype "passive"))
      (node (ref "T11") (pin "B") (pinfunction "B_B") (pintype "passive"))
    )
    (net (code "79") (name "Net-(R12-Pad2)") (class "Default")
      (node (ref "R12") (pin "2") (pinfunction "2_2") (pintype "passive"))
      (node (ref "T12") (pin "B") (pinfunction "B_B") (pintype "passive"))
    )
    (net (code "80") (name "Net-(R13-Pad2)") (class "Default")
      (node (ref "R13") (pin "2") (pinfunction "2_2") (pintype "passive"))
      (node (ref "T13") (pin "B") (pinfunction "B_B") (pintype "passive"))
    )
    (net (code "81") (name "Net-(R14-Pad2)") (class "Default")
      (node (ref "R14") (pin "2") (pinfunction "2_2") (pintype "passive"))
      (node (ref "T14") (pin "B") (pinfunction "B_B") (pintype "passive"))
    )
    (net (code "82") (name "Net-(R15-Pad2)") (class "Default")
      (node (ref "R15") (pin "2") (pinfunction "2_2") (pintype "passive"))
      (node (ref "T15") (pin "B") (pinfunction "B_B") (pintype "passive"))
    )
    (net (code "83") (name "Net-(R16-Pad2)") (class "Default")
      (node (ref "R16") (pin "2") (pinfunction "2_2") (pintype "passive"))
      (node (ref "T16") (pin "B") (pinfunction "B_B") (pintype "passive"))
    )
    (net (code "84") (name "Net-(R17-Pad2)") (class "Default")
      (node (ref "R17") (pin "2") (pinfunction "2_2") (pintype "passive"))
      (node (ref "T17") (pin "B") (pinfunction "B_B") (pintype "passive"))
    )
    (net (code "85") (name "Net-(R18-Pad2)") (class "Default")
      (node (ref "R18") (pin "2") (pinfunction "2_2") (pintype "passive"))
      (node (ref "T18") (pin "B") (pinfunction "B_B") (pintype "passive"))
    )
    (net (code "86") (name "Net-(R19-Pad2)") (class "Default")
      (node (ref "R19") (pin "2") (pinfunction "2_2") (pintype "passive"))
      (node (ref "T19") (pin "B") (pinfunction "B_B") (pintype "passive"))
    )
    (net (code "87") (name "Net-(R20-Pad2)") (class "Default")
      (node (ref "R20") (pin "2") (pinfunction "2_2") (pintype "passive"))
      (node (ref "T20") (pin "B") (pinfunction "B_B") (pintype "passive"))
    )
    (net (code "88") (name "Net-(R21-Pad2)") (class "Default")
      (node (ref "R21") (pin "2") (pinfunction "2_2") (pintype "passive"))
      (node (ref "T21") (pin "B") (pinfunction "B_B") (pintype "passive"))
    )
    (net (code "89") (name "Net-(R22-Pad2)") (class "Default")
      (node (ref "R22") (pin "2") (pinfunction "2_2") (pintype "passive"))
      (node (ref "T22") (pin "B") (pinfunction "B_B") (pintype "passive"))
    )
    (net (code "90") (name "Net-(R23-Pad2)") (class "Default")
      (node (ref "R23") (pin "2") (pinfunction "2_2") (pintype "passive"))
      (node (ref "T23") (pin "B") (pinfunction "B_B") (pintype "passive"))
    )
    (net (code "91") (name "Net-(R24-Pad2)") (class "Default")
      (node (ref "R24") (pin "2") (pinfunction "2_2") (pintype "passive"))
      (node (ref "T24") (pin "B") (pinfunction "B_B") (pintype "passive"))
    )
    (net (code "92") (name "Net-(R25-Pad2)") (class "Default")
      (node (ref "R25") (pin "2") (pinfunction "2_2") (pintype "passive"))
      (node (ref "T25") (pin "B") (pinfunction "B_B") (pintype "passive"))
    )
    (net (code "93") (name "Net-(R26-Pad2)") (class "Default")
      (node (ref "R26") (pin "2") (pinfunction "2_2") (pintype "passive"))
      (node (ref "T26") (pin "B") (pinfunction "B_B") (pintype "passive"))
    )
    (net (code "94") (name "Net-(R27-Pad2)") (class "Default")
      (node (ref "R27") (pin "2") (pinfunction "2_2") (pintype "passive"))
      (node (ref "T27") (pin "B") (pinfunction "B_B") (pintype "passive"))
    )
    (net (code "95") (name "Net-(R28-Pad2)") (class "Default")
      (node (ref "R28") (pin "2") (pinfunction "2_2") (pintype "passive"))
      (node (ref "T28") (pin "B") (pinfunction "B_B") (pintype "passive"))
    )
    (net (code "96") (name "unconnected-(IC1A-QH-Pad7)") (class "Default")
      (node (ref "IC1") (pin "7") (pinfunction "QH_7") (pintype "tri_state"))
    )
    (net (code "97") (name "unconnected-(IC2A-QH-Pad7)") (class "Default")
      (node (ref "IC2") (pin "7") (pinfunction "QH_7") (pintype "tri_state"))
    )
    (net (code "98") (name "unconnected-(IC3A-QH-Pad7)") (class "Default")
      (node (ref "IC3") (pin "7") (pinfunction "QH_7") (pintype "tri_state"))
    )
    (net (code "99") (name "unconnected-(IC4A-QH*-Pad9)") (class "Default")
      (node (ref "IC4") (pin "9") (pinfunction "QH*_9") (pintype "tri_state"))
    )
    (net (code "100") (name "unconnected-(IC4A-QH-Pad7)") (class "Default")
      (node (ref "IC4") (pin "7") (pinfunction "QH_7") (pintype "tri_state"))
    )
    (net (code "101") (name "unconnected-(JP3-Pad3)") (class "Default")
      (node (ref "JP3") (pin "3") (pinfunction "3_3") (pintype "passive"))
    )
    (net (code "102") (name "unconnected-(JP3-Pad5)") (class "Default")
      (node (ref "JP3") (pin "5") (pinfunction "5_5") (pintype "passive"))
    )
    (net (code "103") (name "unconnected-(JP3-Pad6)") (class "Default")
      (node (ref "JP3") (pin "6") (pinfunction "6_6") (pintype "passive"))
    )
    (net (code "104") (name "unconnected-(JP3-Pad7)") (class "Default")
      (node (ref "JP3") (pin "7") (pinfunction "7_7") (pintype "passive"))
    )
    (net (code "105") (name "unconnected-(JP3-Pad9)") (class "Default")
      (node (ref "JP3") (pin "9") (pinfunction "9_9") (pintype "passive"))
    )
    (net (code "106") (name "unconnected-(JP3-Pad10)") (class "Default")
      (node (ref "JP3") (pin "10") (pinfunction "10_10") (pintype "passive"))
    )
    (net (code "107") (name "unconnected-(JP3-Pad11)") (class "Default")
      (node (ref "JP3") (pin "11") (pinfunction "11_11") (pintype "passive"))
    )
    (net (code "108") (name "unconnected-(JP4-Pad1)") (class "Default")
      (node (ref "JP4") (pin "1") (pinfunction "1_1") (pintype "passive"))
    )
    (net (code "109") (name "unconnected-(JP4-Pad2)") (class "Default")
      (node (ref "JP4") (pin "2") (pinfunction "2_2") (pintype "passive"))
    )
    (net (code "110") (name "unconnected-(JP4-Pad3)") (class "Default")
      (node (ref "JP4") (pin "3") (pinfunction "3_3") (pintype "passive"))
    )
    (net (code "111") (name "unconnected-(JP4-Pad4)") (class "Default")
      (node (ref "JP4") (pin "4") (pinfunction "4_4") (pintype "passive"))
    )
    (net (code "112") (name "unconnected-(JP4-Pad6)") (class "Default")
      (node (ref "JP4") (pin "6") (pinfunction "6_6") (pintype "passive"))
    )
    (net (code "113") (name "unconnected-(JP4-Pad8)") (class "Default")
      (node (ref "JP4") (pin "8") (pinfunction "8_8") (pintype "passive"))
    )
    (net (code "114") (name "unconnected-(JP4-Pad9)") (class "Default")
      (node (ref "JP4") (pin "9") (pinfunction "9_9") (pintype "passive"))
    )
    (net (code "115") (name "unconnected-(JP4-Pad10)") (class "Default")
      (node (ref "JP4") (pin "10") (pinfunction "10_10") (pintype "passive"))
    )
    (net (code "116") (name "unconnected-(JP4-Pad11)") (class "Default")
      (node (ref "JP4") (pin "11") (pinfunction "11_11") (pintype "passive"))
    )
    (net (code "117") (name "unconnected-(R29-Pad1)") (class "Default")
      (node (ref "R29") (pin "1") (pinfunction "1_1") (pintype "passive"))
    )
    (net (code "118") (name "unconnected-(R29-Pad2)") (class "Default")
      (node (ref "R29") (pin "2") (pinfunction "2_2") (pintype "passive"))
    )
    (net (code "119") (name "unconnected-(R30-Pad1)") (class "Default")
      (node (ref "R30") (pin "1") (pinfunction "1_1") (pintype "passive"))
    )
    (net (code "120") (name "unconnected-(R30-Pad2)") (class "Default")
      (node (ref "R30") (pin "2") (pinfunction "2_2") (pintype "passive"))
    )
    (net (code "121") (name "unconnected-(R31-Pad1)") (class "Default")
      (node (ref "R31") (pin "1") (pinfunction "1_1") (pintype "passive"))
    )
    (net (code "122") (name "unconnected-(R31-Pad2)") (class "Default")
      (node (ref "R31") (pin "2") (pinfunction "2_2") (pintype "passive"))
    )
    (net (code "123") (name "unconnected-(R32-Pad1)") (class "Default")
      (node (ref "R32") (pin "1") (pinfunction "1_1") (pintype "passive"))
    )
    (net (code "124") (name "unconnected-(R32-Pad2)") (class "Default")
      (node (ref "R32") (pin "2") (pinfunction "2_2") (pintype "passive"))
    )
    (net (code "125") (name "unconnected-(R33-Pad1)") (class "Default")
      (node (ref "R33") (pin "1") (pinfunction "1_1") (pintype "passive"))
    )
    (net (code "126") (name "unconnected-(R33-Pad2)") (class "Default")
      (node (ref "R33") (pin "2") (pinfunction "2_2") (pintype "passive"))
    )
    (net (code "127") (name "unconnected-(R34-Pad1)") (class "Default")
      (node (ref "R34") (pin "1") (pinfunction "1_1") (pintype "passive"))
    )
    (net (code "128") (name "unconnected-(R34-Pad2)") (class "Default")
      (node (ref "R34") (pin "2") (pinfunction "2_2") (pintype "passive"))
    )
    (net (code "129") (name "unconnected-(R35-Pad1)") (class "Default")
      (node (ref "R35") (pin "1") (pinfunction "1_1") (pintype "passive"))
    )
    (net (code "130") (name "unconnected-(R35-Pad2)") (class "Default")
      (node (ref "R35") (pin "2") (pinfunction "2_2") (pintype "passive"))
    )
  )
)
